# Mainboard.net
KiCad netlist of a schematic drawn in Altium Designer
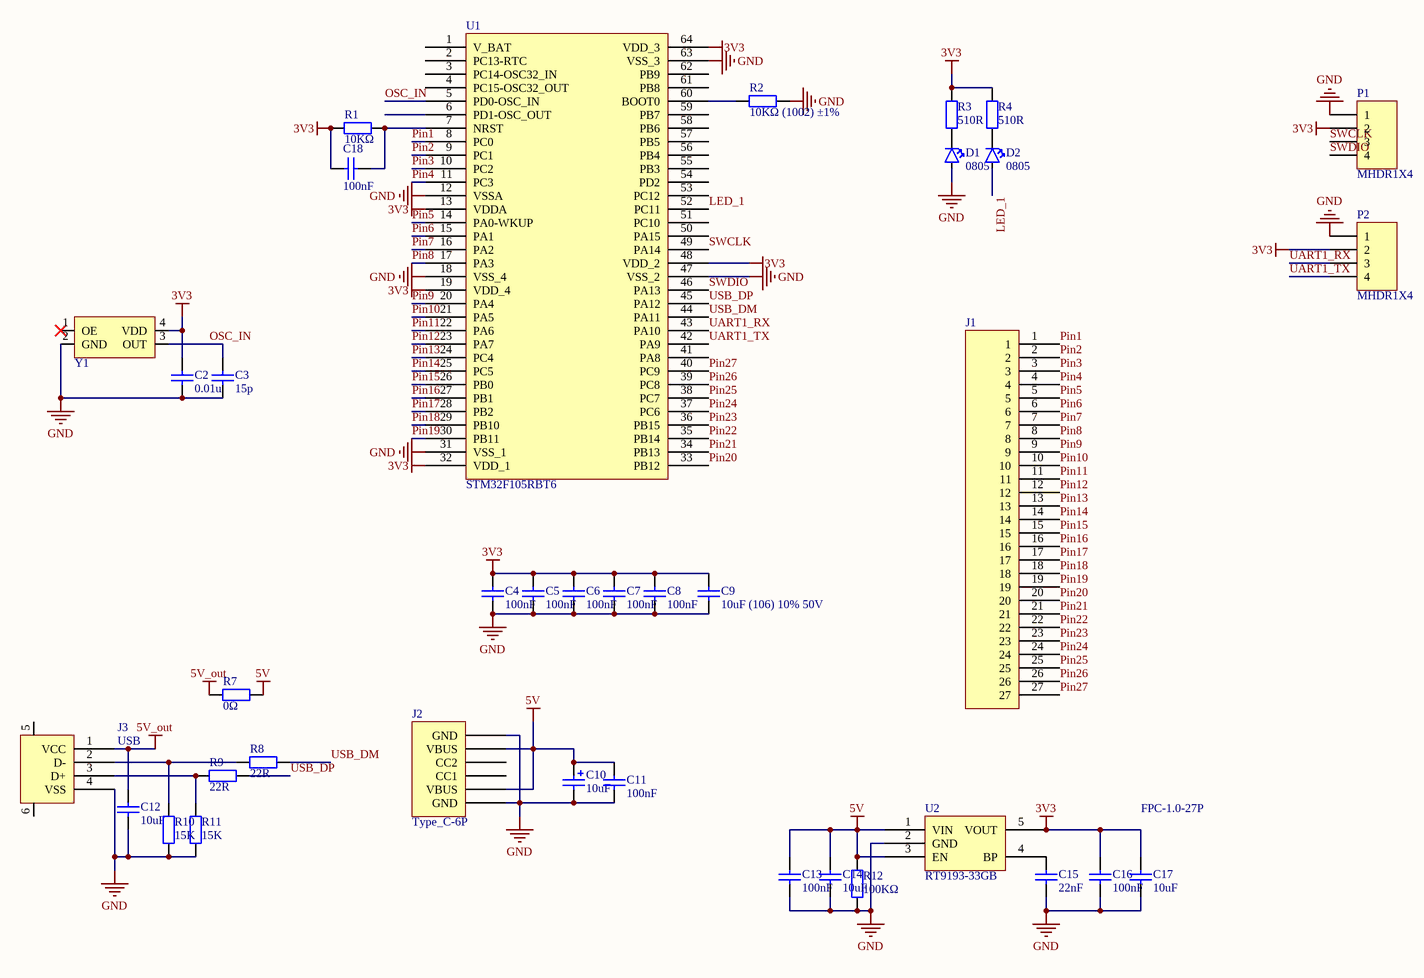
[diagram p0: Mainboard.SchDoc]

(export (version "E")
  (design (tool "Eeschema 10.0.6"))
  (components
    (comp (ref "C2")
      (value "0.01u")
      (footprint "0603_C")
      (description "贴片电容")
      (libsource (lib "Miscellaneous Devices LC") (part "0603 100nF (104) 10% 50V"))
    )
    (comp (ref "C3")
      (value "15p")
      (footprint "0603_C")
      (description "贴片电容")
      (libsource (lib "Miscellaneous Devices LC") (part "0603 100nF (104) 10% 50V"))
    )
    (comp (ref "C4")
      (value "100nF")
      (footprint "0603_C")
      (description "贴片电容")
      (libsource (lib "Miscellaneous Devices LC") (part "0603 100nF (104) 10% 50V"))
    )
    (comp (ref "C5")
      (value "100nF")
      (footprint "0603_C")
      (description "贴片电容")
      (libsource (lib "Miscellaneous Devices LC") (part "0603 100nF (104) 10% 50V"))
    )
    (comp (ref "C6")
      (value "100nF")
      (footprint "0603_C")
      (description "贴片电容")
      (libsource (lib "Miscellaneous Devices LC") (part "0603 100nF (104) 10% 50V"))
    )
    (comp (ref "C7")
      (value "100nF")
      (footprint "0603_C")
      (description "贴片电容")
      (libsource (lib "Miscellaneous Devices LC") (part "0603 100nF (104) 10% 50V"))
    )
    (comp (ref "C8")
      (value "100nF")
      (footprint "0603_C")
      (description "贴片电容")
      (libsource (lib "Miscellaneous Devices LC") (part "0603 100nF (104) 10% 50V"))
    )
    (comp (ref "C9")
      (value "10uF (106) 10% 50V")
      (footprint "1206_C")
      (description "贴片电容")
      (libsource (lib "Miscellaneous Devices LC") (part "1206 10uF (106) 10% 50V"))
    )
    (comp (ref "C10")
      (value "10uF")
      (footprint "CASE-A_3216")
      (description "钽电容")
      (libsource (lib "Miscellaneous Devices LC") (part "3216 10uF (106) 10% 16V"))
    )
    (comp (ref "C11")
      (value "100nF")
      (footprint "0603_C")
      (description "贴片电容")
      (libsource (lib "Miscellaneous Devices LC") (part "0603 100nF (104) 10% 50V"))
    )
    (comp (ref "C12")
      (value "10uF")
      (footprint "1206_C")
      (description "贴片电容")
      (libsource (lib "Miscellaneous Devices LC") (part "1206 10uF (106) 10% 50V"))
    )
    (comp (ref "C13")
      (value "100nF")
      (footprint "0603_C")
      (description "贴片电容")
      (libsource (lib "Miscellaneous Devices LC") (part "0603 100nF (104) 10% 50V"))
    )
    (comp (ref "C14")
      (value "10uF")
      (footprint "1206_C")
      (description "贴片电容")
      (libsource (lib "Miscellaneous Devices LC") (part "1206 10uF (106) 10% 50V"))
    )
    (comp (ref "C15")
      (value "22nF")
      (footprint "0603_C")
      (description "贴片电容")
      (libsource (lib "Miscellaneous Devices LC") (part "0603 100nF (104) 10% 50V"))
    )
    (comp (ref "C16")
      (value "100nF")
      (footprint "0603_C")
      (description "贴片电容")
      (libsource (lib "Miscellaneous Devices LC") (part "0603 100nF (104) 10% 50V"))
    )
    (comp (ref "C17")
      (value "10uF")
      (footprint "1206_C")
      (description "贴片电容")
      (libsource (lib "Miscellaneous Devices LC") (part "1206 10uF (106) 10% 50V"))
    )
    (comp (ref "C18")
      (value "100nF")
      (footprint "0603_C")
      (description "贴片电容")
      (libsource (lib "Miscellaneous Devices LC") (part "0603 100nF (104) 10% 50V"))
    )
    (comp (ref "D1")
      (value "0805")
      (footprint "0805-LED")
      (libsource (lib "CRSN_Common_Parts") (part "LED0805"))
    )
    (comp (ref "D2")
      (value "0805")
      (footprint "0805-LED")
      (libsource (lib "CRSN_Common_Parts") (part "LED0805"))
    )
    (comp (ref "J1")
      (value "FPC-1.0-27P")
      (footprint "FPC-1.0-27P")
      (libsource (lib "Chenqs") (part "FPC-1.0-27P"))
    )
    (comp (ref "J2")
      (value "Type_C-6P")
      (footprint "Type_C-6P")
      (libsource (lib "Type_C") (part "Type_C-6P"))
    )
    (comp (ref "J3")
      (value "USB")
      (footprint "USB_A1")
      (description "USB接口")
      (libsource (lib "Chenqs") (part "USB"))
    )
    (comp (ref "P1")
      (value "MHDR1X4")
      (footprint "MHDR1X4")
      (description "Header, 4-Pin")
      (fields (field (name "PUBLISHER") "Altium Limited"))
      (libsource (lib "Miscellaneous Connectors") (part "MHDR1X4"))
    )
    (comp (ref "P2")
      (value "MHDR1X4")
      (footprint "MHDR1X4")
      (description "Header, 4-Pin")
      (fields (field (name "PUBLISHER") "Altium Limited"))
      (libsource (lib "Miscellaneous Connectors") (part "MHDR1X4"))
    )
    (comp (ref "R1")
      (value "10KΩ")
      (footprint "0603_R")
      (description "贴片电阻")
      (libsource (lib "Miscellaneous Devices LC") (part "0603 10KΩ (1002) 1%"))
    )
    (comp (ref "R2")
      (value "10KΩ (1002) ±1%")
      (footprint "0603_R")
      (description "贴片电阻")
      (libsource (lib "") (part "0603 10KΩ (1002) 1%_3"))
    )
    (comp (ref "R3")
      (value "510R")
      (footprint "0603_R")
      (description "贴片电阻")
      (libsource (lib "") (part "0603 10KΩ (1002) 1%_1"))
    )
    (comp (ref "R4")
      (value "510R")
      (footprint "0603_R")
      (description "贴片电阻")
      (libsource (lib "") (part "0603 10KΩ (1002) 1%_1"))
    )
    (comp (ref "R7")
      (value "0Ω")
      (footprint "0603_R")
      (description "贴片电阻")
      (libsource (lib "Miscellaneous Devices LC") (part "0603 0Ω (0R0) 1%"))
    )
    (comp (ref "R8")
      (value "22R")
      (footprint "0603_R")
      (description "贴片电阻")
      (libsource (lib "Miscellaneous Devices LC") (part "0603 10KΩ (1002) 1%"))
    )
    (comp (ref "R9")
      (value "22R")
      (footprint "0603_R")
      (description "贴片电阻")
      (libsource (lib "Miscellaneous Devices LC") (part "0603 10KΩ (1002) 1%"))
    )
    (comp (ref "R10")
      (value "15K")
      (footprint "0603_R")
      (description "贴片电阻")
      (libsource (lib "") (part "0603 10KΩ (1002) 1%_2"))
    )
    (comp (ref "R11")
      (value "15K")
      (footprint "0603_R")
      (description "贴片电阻")
      (libsource (lib "") (part "0603 10KΩ (1002) 1%_2"))
    )
    (comp (ref "R12")
      (value "100KΩ")
      (footprint "0603_R")
      (description "贴片电阻")
      (libsource (lib "Miscellaneous Devices LC") (part "0603 100KΩ (1003) 1%"))
    )
    (comp (ref "U1")
      (value "STM32F105RBT6")
      (footprint "LQFP-64_10x10x05P")
      (libsource (lib "Chenqs") (part "STM32F105RBT6"))
    )
    (comp (ref "U2")
      (value "RT9193-33GB")
      (footprint "SOT23-5")
      (libsource (lib "Chenqs") (part "RT9193-33GB"))
    )
    (comp (ref "Y1")
      (value "XATLS")
      (footprint "XTAL-3225")
      (description "贴片有源晶振")
      (libsource (lib "Chenqs") (part "XATLS"))
    )
  )
  (nets
    (net (code "1") (name "/LED_1") (class "Default")
      (node (ref "D2") (pin "2") (pintype "passive"))
      (node (ref "U1") (pin "52") (pinfunction "PC11_52") (pintype "passive"))
    )
    (net (code "2") (name "/OSC_IN") (class "Default")
      (node (ref "C3") (pin "2") (pinfunction "2_2") (pintype "passive"))
      (node (ref "U1") (pin "5") (pinfunction "PD0-OSC_IN_5") (pintype "passive"))
      (node (ref "Y1") (pin "3") (pinfunction "OUT_3") (pintype "passive"))
    )
    (net (code "3") (name "/Pin1") (class "Default")
      (node (ref "J1") (pin "1") (pinfunction "1_1") (pintype "passive"))
      (node (ref "U1") (pin "8") (pinfunction "PC0_8") (pintype "passive"))
    )
    (net (code "4") (name "/Pin2") (class "Default")
      (node (ref "J1") (pin "2") (pinfunction "2_2") (pintype "passive"))
      (node (ref "U1") (pin "9") (pinfunction "PC1_9") (pintype "passive"))
    )
    (net (code "5") (name "/Pin3") (class "Default")
      (node (ref "J1") (pin "3") (pinfunction "3_3") (pintype "passive"))
      (node (ref "U1") (pin "10") (pinfunction "PC2_10") (pintype "passive"))
    )
    (net (code "6") (name "/Pin4") (class "Default")
      (node (ref "J1") (pin "4") (pinfunction "4_4") (pintype "passive"))
      (node (ref "U1") (pin "11") (pinfunction "PC3_11") (pintype "passive"))
    )
    (net (code "7") (name "/Pin5") (class "Default")
      (node (ref "J1") (pin "5") (pinfunction "5_5") (pintype "passive"))
      (node (ref "U1") (pin "14") (pinfunction "PA0-WKUP_14") (pintype "passive"))
    )
    (net (code "8") (name "/Pin6") (class "Default")
      (node (ref "J1") (pin "6") (pinfunction "6_6") (pintype "passive"))
      (node (ref "U1") (pin "15") (pinfunction "PA1_15") (pintype "passive"))
    )
    (net (code "9") (name "/Pin7") (class "Default")
      (node (ref "J1") (pin "7") (pinfunction "7_7") (pintype "passive"))
      (node (ref "U1") (pin "16") (pinfunction "PA2_16") (pintype "passive"))
    )
    (net (code "10") (name "/Pin8") (class "Default")
      (node (ref "J1") (pin "8") (pinfunction "8_8") (pintype "passive"))
      (node (ref "U1") (pin "17") (pinfunction "PA3_17") (pintype "passive"))
    )
    (net (code "11") (name "/Pin9") (class "Default")
      (node (ref "J1") (pin "9") (pinfunction "9_9") (pintype "passive"))
      (node (ref "U1") (pin "20") (pinfunction "PA4_20") (pintype "passive"))
    )
    (net (code "12") (name "/Pin10") (class "Default")
      (node (ref "J1") (pin "10") (pinfunction "10_10") (pintype "passive"))
      (node (ref "U1") (pin "21") (pinfunction "PA5_21") (pintype "passive"))
    )
    (net (code "13") (name "/Pin11") (class "Default")
      (node (ref "J1") (pin "11") (pinfunction "11_11") (pintype "passive"))
      (node (ref "U1") (pin "22") (pinfunction "PA6_22") (pintype "passive"))
    )
    (net (code "14") (name "/Pin12") (class "Default")
      (node (ref "J1") (pin "12") (pinfunction "12_12") (pintype "passive"))
      (node (ref "U1") (pin "23") (pinfunction "PA7_23") (pintype "passive"))
    )
    (net (code "15") (name "/Pin13") (class "Default")
      (node (ref "J1") (pin "13") (pinfunction "13_13") (pintype "passive"))
      (node (ref "U1") (pin "24") (pinfunction "PC4_24") (pintype "passive"))
    )
    (net (code "16") (name "/Pin14") (class "Default")
      (node (ref "J1") (pin "14") (pinfunction "14_14") (pintype "passive"))
      (node (ref "U1") (pin "25") (pinfunction "PC5_25") (pintype "passive"))
    )
    (net (code "17") (name "/Pin15") (class "Default")
      (node (ref "J1") (pin "15") (pinfunction "15_15") (pintype "passive"))
      (node (ref "U1") (pin "26") (pinfunction "PB0_26") (pintype "passive"))
    )
    (net (code "18") (name "/Pin16") (class "Default")
      (node (ref "J1") (pin "16") (pinfunction "16_16") (pintype "passive"))
      (node (ref "U1") (pin "27") (pinfunction "PB1_27") (pintype "passive"))
    )
    (net (code "19") (name "/Pin17") (class "Default")
      (node (ref "J1") (pin "17") (pinfunction "17_17") (pintype "passive"))
      (node (ref "U1") (pin "28") (pinfunction "PB2_28") (pintype "passive"))
    )
    (net (code "20") (name "/Pin18") (class "Default")
      (node (ref "J1") (pin "18") (pinfunction "18_18") (pintype "passive"))
      (node (ref "U1") (pin "29") (pinfunction "PB10_29") (pintype "passive"))
    )
    (net (code "21") (name "/Pin19") (class "Default")
      (node (ref "J1") (pin "19") (pinfunction "19_19") (pintype "passive"))
      (node (ref "U1") (pin "30") (pinfunction "PB11_30") (pintype "passive"))
    )
    (net (code "22") (name "/Pin20") (class "Default")
      (node (ref "J1") (pin "20") (pinfunction "20_20") (pintype "passive"))
      (node (ref "U1") (pin "33") (pinfunction "PB12_33") (pintype "passive"))
    )
    (net (code "23") (name "/Pin21") (class "Default")
      (node (ref "J1") (pin "21") (pinfunction "21_21") (pintype "passive"))
      (node (ref "U1") (pin "34") (pinfunction "PB13_34") (pintype "passive"))
    )
    (net (code "24") (name "/Pin22") (class "Default")
      (node (ref "J1") (pin "22") (pinfunction "22_22") (pintype "passive"))
      (node (ref "U1") (pin "35") (pinfunction "PB14_35") (pintype "passive"))
    )
    (net (code "25") (name "/Pin23") (class "Default")
      (node (ref "J1") (pin "23") (pinfunction "23_23") (pintype "passive"))
      (node (ref "U1") (pin "36") (pinfunction "PB15_36") (pintype "passive"))
    )
    (net (code "26") (name "/Pin24") (class "Default")
      (node (ref "J1") (pin "24") (pinfunction "24_24") (pintype "passive"))
      (node (ref "U1") (pin "37") (pinfunction "PC6_37") (pintype "passive"))
    )
    (net (code "27") (name "/Pin25") (class "Default")
      (node (ref "J1") (pin "25") (pinfunction "25_25") (pintype "passive"))
      (node (ref "U1") (pin "38") (pinfunction "PC7_38") (pintype "passive"))
    )
    (net (code "28") (name "/Pin26") (class "Default")
      (node (ref "J1") (pin "26") (pinfunction "26_26") (pintype "passive"))
      (node (ref "U1") (pin "39") (pinfunction "PC8_39") (pintype "passive"))
    )
    (net (code "29") (name "/Pin27") (class "Default")
      (node (ref "J1") (pin "27") (pinfunction "27_27") (pintype "passive"))
      (node (ref "U1") (pin "40") (pinfunction "PC9_40") (pintype "passive"))
    )
    (net (code "30") (name "/SWCLK") (class "Default")
      (node (ref "P1") (pin "3") (pinfunction "3_3") (pintype "passive"))
      (node (ref "U1") (pin "49") (pinfunction "PA14_49") (pintype "passive"))
    )
    (net (code "31") (name "/SWDIO") (class "Default")
      (node (ref "P1") (pin "4") (pinfunction "4_4") (pintype "passive"))
      (node (ref "U1") (pin "46") (pinfunction "PA13_46") (pintype "passive"))
    )
    (net (code "32") (name "/UART1_RX") (class "Default")
      (node (ref "P2") (pin "3") (pinfunction "3_3") (pintype "passive"))
      (node (ref "U1") (pin "43") (pinfunction "PA10_43") (pintype "passive"))
    )
    (net (code "33") (name "/UART1_TX") (class "Default")
      (node (ref "P2") (pin "4") (pinfunction "4_4") (pintype "passive"))
      (node (ref "U1") (pin "42") (pinfunction "PA9_42") (pintype "passive"))
    )
    (net (code "34") (name "/USB_DM") (class "Default")
      (node (ref "R8") (pin "1") (pinfunction "1_1") (pintype "passive"))
      (node (ref "U1") (pin "44") (pinfunction "PA11_44") (pintype "passive"))
    )
    (net (code "35") (name "/USB_DP") (class "Default")
      (node (ref "R9") (pin "1") (pinfunction "1_1") (pintype "passive"))
      (node (ref "U1") (pin "45") (pinfunction "PA12_45") (pintype "passive"))
    )
    (net (code "36") (name "3V3") (class "Default")
      (node (ref "C16") (pin "2") (pinfunction "2_2") (pintype "passive"))
      (node (ref "C17") (pin "2") (pinfunction "2_2") (pintype "passive"))
      (node (ref "C18") (pin "2") (pinfunction "2_2") (pintype "passive"))
      (node (ref "C2") (pin "2") (pinfunction "2_2") (pintype "passive"))
      (node (ref "C4") (pin "2") (pinfunction "2_2") (pintype "passive"))
      (node (ref "C5") (pin "2") (pinfunction "2_2") (pintype "passive"))
      (node (ref "C6") (pin "2") (pinfunction "2_2") (pintype "passive"))
      (node (ref "C7") (pin "2") (pinfunction "2_2") (pintype "passive"))
      (node (ref "C8") (pin "2") (pinfunction "2_2") (pintype "passive"))
      (node (ref "C9") (pin "2") (pinfunction "2_2") (pintype "passive"))
      (node (ref "P1") (pin "2") (pinfunction "2_2") (pintype "passive"))
      (node (ref "P2") (pin "2") (pinfunction "2_2") (pintype "passive"))
      (node (ref "R1") (pin "2") (pinfunction "2_2") (pintype "passive"))
      (node (ref "R3") (pin "2") (pinfunction "2_2") (pintype "passive"))
      (node (ref "R4") (pin "2") (pinfunction "2_2") (pintype "passive"))
      (node (ref "U1") (pin "13") (pinfunction "VDDA_13") (pintype "passive"))
      (node (ref "U1") (pin "19") (pinfunction "VDD_4_19") (pintype "passive"))
      (node (ref "U1") (pin "32") (pinfunction "VDD_1_32") (pintype "passive"))
      (node (ref "U1") (pin "48") (pinfunction "VDD_2_48") (pintype "passive"))
      (node (ref "U1") (pin "64") (pinfunction "VDD_3_64") (pintype "passive"))
      (node (ref "U2") (pin "5") (pinfunction "VOUT_5") (pintype "passive"))
      (node (ref "Y1") (pin "4") (pinfunction "VDD_4") (pintype "passive"))
    )
    (net (code "37") (name "5V") (class "Default")
      (node (ref "C10") (pin "1") (pinfunction "1_1") (pintype "passive"))
      (node (ref "C11") (pin "2") (pinfunction "2_2") (pintype "passive"))
      (node (ref "C13") (pin "2") (pinfunction "2_2") (pintype "passive"))
      (node (ref "C14") (pin "2") (pinfunction "2_2") (pintype "passive"))
      (node (ref "J2") (pin "A9") (pinfunction "VBUS_A9") (pintype "passive"))
      (node (ref "J2") (pin "B9") (pinfunction "VBUS_B9") (pintype "passive"))
      (node (ref "R12") (pin "1") (pinfunction "1_1") (pintype "passive"))
      (node (ref "R7") (pin "2") (pinfunction "2_2") (pintype "passive"))
      (node (ref "U2") (pin "1") (pinfunction "VIN_1") (pintype "passive"))
      (node (ref "U2") (pin "3") (pinfunction "EN_3") (pintype "passive"))
    )
    (net (code "38") (name "5V_out") (class "Default")
      (node (ref "C12") (pin "2") (pinfunction "2_2") (pintype "passive"))
      (node (ref "J3") (pin "1") (pinfunction "VCC_1") (pintype "passive"))
      (node (ref "R7") (pin "1") (pinfunction "1_1") (pintype "passive"))
    )
    (net (code "39") (name "GND") (class "Default")
      (node (ref "C10") (pin "2") (pinfunction "2_2") (pintype "passive"))
      (node (ref "C11") (pin "1") (pinfunction "1_1") (pintype "passive"))
      (node (ref "C12") (pin "1") (pinfunction "1_1") (pintype "passive"))
      (node (ref "C13") (pin "1") (pinfunction "1_1") (pintype "passive"))
      (node (ref "C14") (pin "1") (pinfunction "1_1") (pintype "passive"))
      (node (ref "C15") (pin "1") (pinfunction "1_1") (pintype "passive"))
      (node (ref "C16") (pin "1") (pinfunction "1_1") (pintype "passive"))
      (node (ref "C17") (pin "1") (pinfunction "1_1") (pintype "passive"))
      (node (ref "C2") (pin "1") (pinfunction "1_1") (pintype "passive"))
      (node (ref "C3") (pin "1") (pinfunction "1_1") (pintype "passive"))
      (node (ref "C4") (pin "1") (pinfunction "1_1") (pintype "passive"))
      (node (ref "C5") (pin "1") (pinfunction "1_1") (pintype "passive"))
      (node (ref "C6") (pin "1") (pinfunction "1_1") (pintype "passive"))
      (node (ref "C7") (pin "1") (pinfunction "1_1") (pintype "passive"))
      (node (ref "C8") (pin "1") (pinfunction "1_1") (pintype "passive"))
      (node (ref "C9") (pin "1") (pinfunction "1_1") (pintype "passive"))
      (node (ref "D1") (pin "2") (pintype "passive"))
      (node (ref "J2") (pin "A12") (pinfunction "GND_A12") (pintype "passive"))
      (node (ref "J2") (pin "B12") (pinfunction "GND_B12") (pintype "passive"))
      (node (ref "J3") (pin "4") (pinfunction "VSS_4") (pintype "passive"))
      (node (ref "P1") (pin "1") (pinfunction "1_1") (pintype "passive"))
      (node (ref "P2") (pin "1") (pinfunction "1_1") (pintype "passive"))
      (node (ref "R10") (pin "2") (pinfunction "2_2") (pintype "passive"))
      (node (ref "R11") (pin "2") (pinfunction "2_2") (pintype "passive"))
      (node (ref "R12") (pin "2") (pinfunction "2_2") (pintype "passive"))
      (node (ref "R2") (pin "2") (pinfunction "2_2") (pintype "passive"))
      (node (ref "U1") (pin "12") (pinfunction "VSSA_12") (pintype "passive"))
      (node (ref "U1") (pin "18") (pinfunction "VSS_4_18") (pintype "passive"))
      (node (ref "U1") (pin "31") (pinfunction "VSS_1_31") (pintype "passive"))
      (node (ref "U1") (pin "47") (pinfunction "VSS_2_47") (pintype "passive"))
      (node (ref "U1") (pin "63") (pinfunction "VSS_3_63") (pintype "passive"))
      (node (ref "U2") (pin "2") (pinfunction "GND_2") (pintype "passive"))
      (node (ref "Y1") (pin "2") (pinfunction "GND_2") (pintype "passive"))
    )
    (net (code "40") (name "Net-(D1-Pad1)") (class "Default")
      (node (ref "D1") (pin "1") (pintype "passive"))
      (node (ref "R3") (pin "1") (pinfunction "1_1") (pintype "passive"))
    )
    (net (code "41") (name "Net-(D2-Pad1)") (class "Default")
      (node (ref "D2") (pin "1") (pintype "passive"))
      (node (ref "R4") (pin "1") (pinfunction "1_1") (pintype "passive"))
    )
    (net (code "42") (name "Net-(J3-D+)") (class "Default")
      (node (ref "J3") (pin "3") (pinfunction "D+_3") (pintype "passive"))
      (node (ref "R11") (pin "1") (pinfunction "1_1") (pintype "passive"))
      (node (ref "R9") (pin "2") (pinfunction "2_2") (pintype "passive"))
    )
    (net (code "43") (name "Net-(J3-D-)") (class "Default")
      (node (ref "J3") (pin "2") (pinfunction "D-_2") (pintype "passive"))
      (node (ref "R10") (pin "1") (pinfunction "1_1") (pintype "passive"))
      (node (ref "R8") (pin "2") (pinfunction "2_2") (pintype "passive"))
    )
    (net (code "44") (name "Net-(U1-BOOT0)") (class "Default")
      (node (ref "R2") (pin "1") (pinfunction "1_1") (pintype "passive"))
      (node (ref "U1") (pin "60") (pinfunction "BOOT0_60") (pintype "passive"))
    )
    (net (code "45") (name "Net-(U1-NRST)") (class "Default")
      (node (ref "C18") (pin "1") (pinfunction "1_1") (pintype "passive"))
      (node (ref "R1") (pin "1") (pinfunction "1_1") (pintype "passive"))
      (node (ref "U1") (pin "7") (pinfunction "NRST_7") (pintype "passive"))
    )
    (net (code "46") (name "Net-(U2-BP)") (class "Default")
      (node (ref "C15") (pin "2") (pinfunction "2_2") (pintype "passive"))
      (node (ref "U2") (pin "4") (pinfunction "BP_4") (pintype "passive"))
    )
    (net (code "47") (name "unconnected-(J2-CC1-PadA5)") (class "Default")
      (node (ref "J2") (pin "A5") (pinfunction "CC1_A5") (pintype "passive"))
    )
    (net (code "48") (name "unconnected-(J2-CC2-PadB5)") (class "Default")
      (node (ref "J2") (pin "B5") (pinfunction "CC2_B5") (pintype "passive"))
    )
    (net (code "49") (name "unconnected-(J3-Pad5)") (class "Default")
      (node (ref "J3") (pin "5") (pinfunction "5_5") (pintype "passive"))
    )
    (net (code "50") (name "unconnected-(J3-Pad6)") (class "Default")
      (node (ref "J3") (pin "6") (pinfunction "6_6") (pintype "passive"))
    )
    (net (code "51") (name "unconnected-(U1-PA8-Pad41)") (class "Default")
      (node (ref "U1") (pin "41") (pinfunction "PA8_41") (pintype "passive"))
    )
    (net (code "52") (name "unconnected-(U1-PA15-Pad50)") (class "Default")
      (node (ref "U1") (pin "50") (pinfunction "PA15_50") (pintype "passive"))
    )
    (net (code "53") (name "unconnected-(U1-PB3-Pad55)") (class "Default")
      (node (ref "U1") (pin "55") (pinfunction "PB3_55") (pintype "passive"))
    )
    (net (code "54") (name "unconnected-(U1-PB4-Pad56)") (class "Default")
      (node (ref "U1") (pin "56") (pinfunction "PB4_56") (pintype "passive"))
    )
    (net (code "55") (name "unconnected-(U1-PB5-Pad57)") (class "Default")
      (node (ref "U1") (pin "57") (pinfunction "PB5_57") (pintype "passive"))
    )
    (net (code "56") (name "unconnected-(U1-PB6-Pad58)") (class "Default")
      (node (ref "U1") (pin "58") (pinfunction "PB6_58") (pintype "passive"))
    )
    (net (code "57") (name "unconnected-(U1-PB7-Pad59)") (class "Default")
      (node (ref "U1") (pin "59") (pinfunction "PB7_59") (pintype "passive"))
    )
    (net (code "58") (name "unconnected-(U1-PB8-Pad61)") (class "Default")
      (node (ref "U1") (pin "61") (pinfunction "PB8_61") (pintype "passive"))
    )
    (net (code "59") (name "unconnected-(U1-PB9-Pad62)") (class "Default")
      (node (ref "U1") (pin "62") (pinfunction "PB9_62") (pintype "passive"))
    )
    (net (code "60") (name "unconnected-(U1-PC10-Pad51)") (class "Default")
      (node (ref "U1") (pin "51") (pinfunction "PC10_51") (pintype "passive"))
    )
    (net (code "61") (name "unconnected-(U1-PC12-Pad53)") (class "Default")
      (node (ref "U1") (pin "53") (pinfunction "PC12_53") (pintype "passive"))
    )
    (net (code "62") (name "unconnected-(U1-PC13-RTC-Pad2)") (class "Default")
      (node (ref "U1") (pin "2") (pinfunction "PC13-RTC_2") (pintype "passive"))
    )
    (net (code "63") (name "unconnected-(U1-PC14-OSC32_IN-Pad3)") (class "Default")
      (node (ref "U1") (pin "3") (pinfunction "PC14-OSC32_IN_3") (pintype "passive"))
    )
    (net (code "64") (name "unconnected-(U1-PC15-OSC32_OUT-Pad4)") (class "Default")
      (node (ref "U1") (pin "4") (pinfunction "PC15-OSC32_OUT_4") (pintype "passive"))
    )
    (net (code "65") (name "unconnected-(U1-PD1-OSC_OUT-Pad6)") (class "Default")
      (node (ref "U1") (pin "6") (pinfunction "PD1-OSC_OUT_6") (pintype "passive"))
    )
    (net (code "66") (name "unconnected-(U1-PD2-Pad54)") (class "Default")
      (node (ref "U1") (pin "54") (pinfunction "PD2_54") (pintype "passive"))
    )
    (net (code "67") (name "unconnected-(U1-V_BAT-Pad1)") (class "Default")
      (node (ref "U1") (pin "1") (pinfunction "V_BAT_1") (pintype "passive"))
    )
    (net (code "68") (name "unconnected-(Y1-OE-Pad1)") (class "Default")
      (node (ref "Y1") (pin "1") (pinfunction "OE_1") (pintype "passive+no_connect"))
    )
  )
)
